# radio2.net
KiCad netlist of a schematic drawn in EAGLE
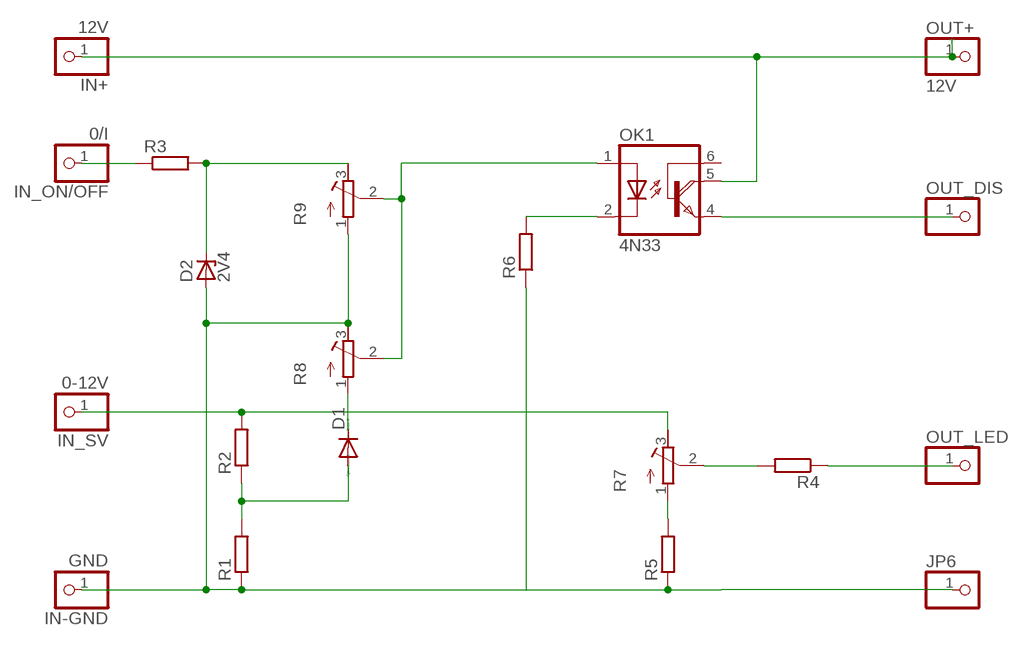
[diagram p0: schematic, sheet 1]

(export (version "E")
  (design (tool "Eeschema 10.0.6"))
  (components
    (comp (ref "D1")
      (value "1N4004")
      (footprint "eagle-import:DO41-10")
      (libsource (lib "eagle-import") (part "1N4004"))
    )
    (comp (ref "D2")
      (value "2V4")
      (footprint "eagle-import:DO35Z10")
      (libsource (lib "eagle-import") (part "1N821"))
    )
    (comp (ref "IN+")
      (value "12V")
      (footprint "eagle-import:1X01")
      (libsource (lib "eagle-import") (part "PINHD-1X1"))
    )
    (comp (ref "IN-GND")
      (value "GND")
      (footprint "eagle-import:1X01")
      (libsource (lib "eagle-import") (part "PINHD-1X1"))
    )
    (comp (ref "IN_ON/OFF")
      (value "0/I")
      (footprint "eagle-import:1X01")
      (libsource (lib "eagle-import") (part "PINHD-1X1"))
    )
    (comp (ref "IN_SV")
      (value "0-12V")
      (footprint "eagle-import:1X01")
      (libsource (lib "eagle-import") (part "PINHD-1X1"))
    )
    (comp (ref "JP6")
      (value "PINHD-1X1")
      (footprint "eagle-import:1X01")
      (libsource (lib "eagle-import") (part "PINHD-1X1"))
    )
    (comp (ref "OK1")
      (value "4N33")
      (footprint "eagle-import:DIL06")
      (fields (field (name "MF") "VISHAY/TELEFUNKEN"))
      (libsource (lib "eagle-import") (part "4N33"))
    )
    (comp (ref "OUT+")
      (value "12V")
      (footprint "eagle-import:1X01")
      (libsource (lib "eagle-import") (part "PINHD-1X1"))
    )
    (comp (ref "OUT_DIS")
      (value "PINHD-1X1")
      (footprint "eagle-import:1X01")
      (libsource (lib "eagle-import") (part "PINHD-1X1"))
    )
    (comp (ref "OUT_LED")
      (value "PINHD-1X1")
      (footprint "eagle-import:1X01")
      (libsource (lib "eagle-import") (part "PINHD-1X1"))
    )
    (comp (ref "R1")
      (value "R-EU_0207/7")
      (footprint "eagle-import:0207_7")
      (libsource (lib "eagle-import") (part "R-EU_0207/7"))
    )
    (comp (ref "R2")
      (value "R-EU_0207/7")
      (footprint "eagle-import:0207_7")
      (libsource (lib "eagle-import") (part "R-EU_0207/7"))
    )
    (comp (ref "R3")
      (value "R-EU_0207/7")
      (footprint "eagle-import:0207_7")
      (libsource (lib "eagle-import") (part "R-EU_0207/7"))
    )
    (comp (ref "R4")
      (value "R-EU_0207/7")
      (footprint "eagle-import:0207_7")
      (libsource (lib "eagle-import") (part "R-EU_0207/7"))
    )
    (comp (ref "R5")
      (value "R-EU_0207/7")
      (footprint "eagle-import:0207_7")
      (libsource (lib "eagle-import") (part "R-EU_0207/7"))
    )
    (comp (ref "R6")
      (value "R-EU_0207/7")
      (footprint "eagle-import:0207_7")
      (libsource (lib "eagle-import") (part "R-EU_0207/7"))
    )
    (comp (ref "R7")
      (value "R-TRIMM3339P")
      (footprint "eagle-import:RTRIM3339P")
      (libsource (lib "eagle-import") (part "R-TRIMM3339P"))
    )
    (comp (ref "R8")
      (value "R-TRIMM3339P")
      (footprint "eagle-import:RTRIM3339P")
      (libsource (lib "eagle-import") (part "R-TRIMM3339P"))
    )
    (comp (ref "R9")
      (value "R-TRIMM3339P")
      (footprint "eagle-import:RTRIM3339P")
      (libsource (lib "eagle-import") (part "R-TRIMM3339P"))
    )
  )
  (nets
    (net (code "1") (name "Net-(D1-PadA)") (class "Default")
      (node (ref "D1") (pin "A") (pinfunction "A_A") (pintype "passive"))
      (node (ref "R1") (pin "2") (pinfunction "2_2") (pintype "passive"))
      (node (ref "R2") (pin "1") (pinfunction "1_1") (pintype "passive"))
    )
    (net (code "2") (name "Net-(IN_ON/OFF-Pad1)") (class "Default")
      (node (ref "IN_ON/OFF") (pin "1") (pinfunction "1_1") (pintype "passive"))
      (node (ref "R3") (pin "1") (pinfunction "1_1") (pintype "passive"))
    )
    (net (code "3") (name "Net-(OK1-A)") (class "Default")
      (node (ref "OK1") (pin "1") (pinfunction "A_1") (pintype "passive"))
      (node (ref "R8") (pin "2") (pinfunction "S_2") (pintype "passive"))
      (node (ref "R9") (pin "2") (pinfunction "S_2") (pintype "passive"))
    )
    (net (code "4") (name "Net-(OK1-C)") (class "Default")
      (node (ref "OK1") (pin "2") (pinfunction "C_2") (pintype "passive"))
      (node (ref "R6") (pin "2") (pinfunction "2_2") (pintype "passive"))
    )
    (net (code "5") (name "Net-(OK1-COL)") (class "Default")
      (node (ref "IN+") (pin "1") (pinfunction "1_1") (pintype "passive"))
      (node (ref "OK1") (pin "5") (pinfunction "COL_5") (pintype "passive"))
      (node (ref "OUT+") (pin "1") (pinfunction "1_1") (pintype "passive"))
    )
    (net (code "6") (name "Net-(OK1-E)") (class "Default")
      (node (ref "OK1") (pin "4") (pinfunction "E_4") (pintype "passive"))
      (node (ref "OUT_DIS") (pin "1") (pinfunction "1_1") (pintype "passive"))
    )
    (net (code "7") (name "Net-(OUT_LED-Pad1)") (class "Default")
      (node (ref "OUT_LED") (pin "1") (pinfunction "1_1") (pintype "passive"))
      (node (ref "R4") (pin "1") (pinfunction "1_1") (pintype "passive"))
    )
    (net (code "8") (name "Net-(R7-A)") (class "Default")
      (node (ref "R5") (pin "2") (pinfunction "2_2") (pintype "passive"))
      (node (ref "R7") (pin "1") (pinfunction "A_1") (pintype "passive"))
    )
    (net (code "9") (name "Net-(R7-E)") (class "Default")
      (node (ref "IN_SV") (pin "1") (pinfunction "1_1") (pintype "passive"))
      (node (ref "R2") (pin "2") (pinfunction "2_2") (pintype "passive"))
      (node (ref "R7") (pin "3") (pinfunction "E_3") (pintype "passive"))
    )
    (net (code "10") (name "Net-(R7-S)") (class "Default")
      (node (ref "R4") (pin "2") (pinfunction "2_2") (pintype "passive"))
      (node (ref "R7") (pin "2") (pinfunction "S_2") (pintype "passive"))
    )
    (net (code "11") (name "Net-(R8-A)") (class "Default")
      (node (ref "D1") (pin "C") (pinfunction "C_C") (pintype "passive"))
      (node (ref "R8") (pin "1") (pinfunction "A_1") (pintype "passive"))
    )
    (net (code "12") (name "Net-(R8-E)") (class "Default")
      (node (ref "D2") (pin "A") (pinfunction "A_A") (pintype "passive"))
      (node (ref "IN-GND") (pin "1") (pinfunction "1_1") (pintype "passive"))
      (node (ref "JP6") (pin "1") (pinfunction "1_1") (pintype "passive"))
      (node (ref "R1") (pin "1") (pinfunction "1_1") (pintype "passive"))
      (node (ref "R5") (pin "1") (pinfunction "1_1") (pintype "passive"))
      (node (ref "R6") (pin "1") (pinfunction "1_1") (pintype "passive"))
      (node (ref "R8") (pin "3") (pinfunction "E_3") (pintype "passive"))
      (node (ref "R9") (pin "1") (pinfunction "A_1") (pintype "passive"))
    )
    (net (code "13") (name "Net-(R9-E)") (class "Default")
      (node (ref "D2") (pin "C") (pinfunction "C_C") (pintype "passive"))
      (node (ref "R3") (pin "2") (pinfunction "2_2") (pintype "passive"))
      (node (ref "R9") (pin "3") (pinfunction "E_3") (pintype "passive"))
    )
    (net (code "14") (name "unconnected-(OK1-B-Pad6)") (class "Default")
      (node (ref "OK1") (pin "6") (pinfunction "B_6") (pintype "passive"))
    )
  )
)
